# GuitarMultiEffect.net
KiCad netlist of a schematic drawn in EasyEDA
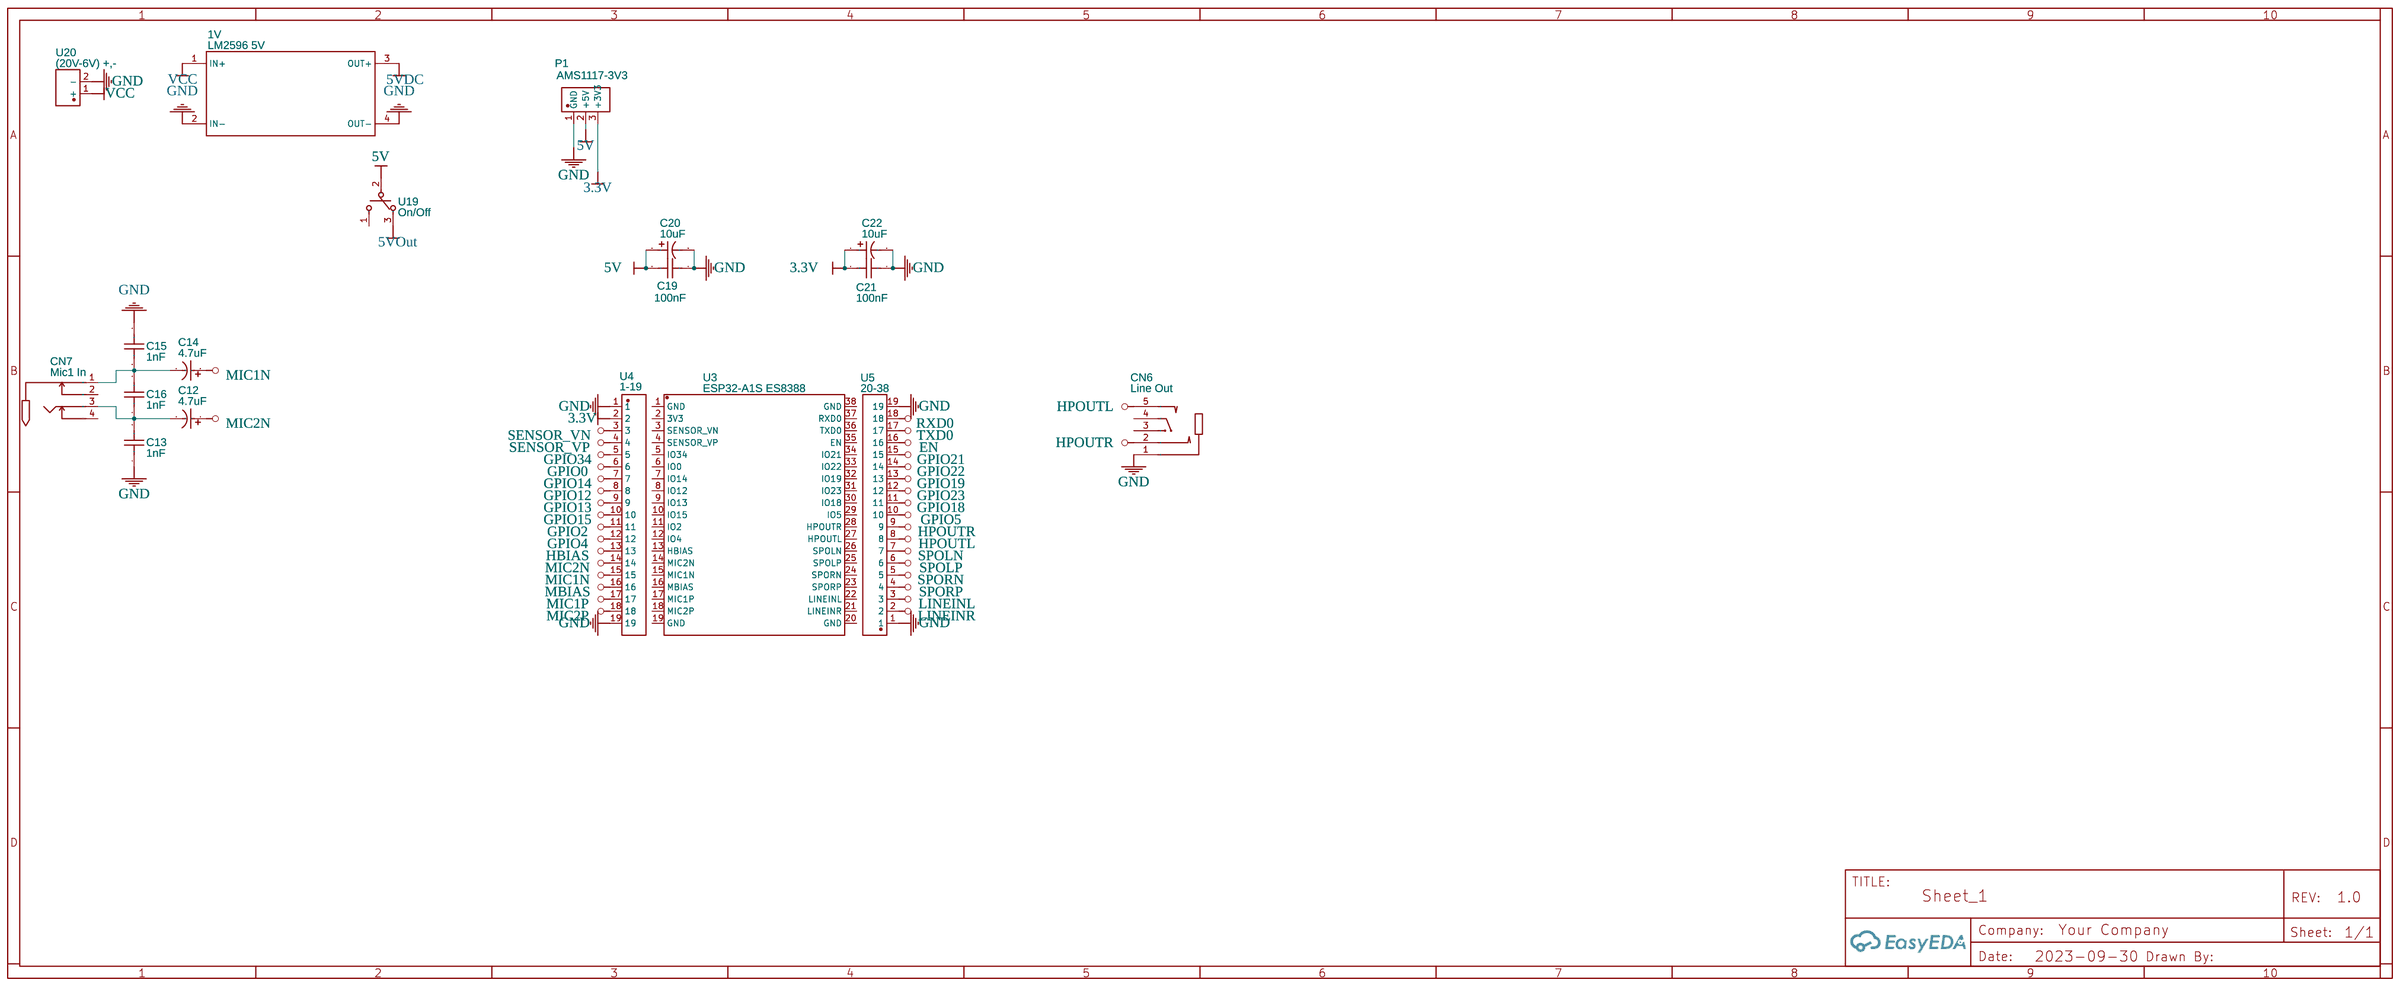
[diagram p0: schematic sheet]

(export (version "E")
  (design (tool "Eeschema 10.0.6"))
  (components
    (comp (ref "1V") (value "LM2596 5V") (libsource (lib "") (part "LM2596")))
    (comp (ref "C12")
      (value "4.7uF")
      (fields
        (field (name "Manufacturer Part") "KM475M050D11RR0VH2FP0")
        (field (name "Manufacturer") "CX(承兴)")
      )
      (libsource (lib "") (part "4.7uF 50V 5*11"))
    )
    (comp (ref "C13")
      (value "1nF")
      (fields (field (name "Manufacturer Part") "R08B1B102KN0B0S0N0") (field (name "Manufacturer") "STE(松田)"))
      (libsource (lib "") (part "R08B1B102KN0B0S0N0_1"))
    )
    (comp (ref "C14")
      (value "4.7uF")
      (fields
        (field (name "Manufacturer Part") "KM475M050D11RR0VH2FP0")
        (field (name "Manufacturer") "CX(承兴)")
      )
      (libsource (lib "") (part "4.7uF 50V 5*11"))
    )
    (comp (ref "C15")
      (value "1nF")
      (fields (field (name "Manufacturer Part") "R08B1B102KN0B0S0N0") (field (name "Manufacturer") "STE(松田)"))
      (libsource (lib "") (part "R08B1B102KN0B0S0N0"))
    )
    (comp (ref "C16")
      (value "1nF")
      (fields (field (name "Manufacturer Part") "R08B1B102KN0B0S0N0") (field (name "Manufacturer") "STE(松田)"))
      (libsource (lib "") (part "R08B1B102KN0B0S0N0_1"))
    )
    (comp (ref "C19")
      (value "100nF")
      (fields (field (name "Manufacturer Part") "CL112J103J0501") (field (name "Manufacturer") "KYET(科雅)"))
      (libsource (lib "") (part "CL112J103J0501"))
    )
    (comp (ref "C20")
      (value "10uF")
      (fields (field (name "Manufacturer Part") "50V10uF CD110") (field (name "Manufacturer") "HRK(鸿瑞凯电子)"))
      (libsource (lib "") (part "50V10UF CD110_C2960373"))
    )
    (comp (ref "C21")
      (value "100nF")
      (fields (field (name "Manufacturer Part") "CL112J103J0501") (field (name "Manufacturer") "KYET(科雅)"))
      (libsource (lib "") (part "CL112J103J0501"))
    )
    (comp (ref "C22")
      (value "10uF")
      (fields (field (name "Manufacturer Part") "50V10uF CD110") (field (name "Manufacturer") "HRK(鸿瑞凯电子)"))
      (libsource (lib "") (part "50V10UF CD110_C2960373"))
    )
    (comp (ref "CN6")
      (value "Line Out")
      (fields
        (field (name "Manufacturer Part") "PJ-3062-HD-R")
        (field (name "Manufacturer") "XKB Connectivity(中国星坤)")
      )
      (libsource (lib "") (part "PJ-3062-HD-R"))
    )
    (comp (ref "CN7")
      (value "Mic1 In")
      (fields (field (name "Manufacturer Part") "CK6.35-3+15-6") (field (name "Manufacturer") "JINJIA(金佳)"))
      (libsource (lib "") (part "CK6.35-3+15-6"))
    )
    (comp (ref "P1")
      (value "AMS1117-3V3")
      (fields (field (name "Manufacturer Part") "M3025V-1x6P") (field (name "Manufacturer") "XFCN"))
      (libsource (lib "") (part "Header 1x3"))
    )
    (comp (ref "U3")
      (value "ESP32-A1S ES8388")
      (fields (field (name "Manufacturer Part") "ESP32-A1S") (field (name "Manufacturer") "Ai-Thinker"))
      (libsource (lib "") (part "ESP32-A1S"))
    )
    (comp (ref "U4")
      (value "1-19")
      (fields
        (field (name "Manufacturer Part") "X1311WV-19J-C18D27")
        (field (name "Manufacturer") "XKB Connectivity(中国星坤)")
      )
      (libsource (lib "") (part "X1311WV-19J-C18D27"))
    )
    (comp (ref "U5")
      (value "20-38")
      (fields
        (field (name "Manufacturer Part") "X1311WV-19J-C18D27")
        (field (name "Manufacturer") "XKB Connectivity(中国星坤)")
      )
      (libsource (lib "") (part "X1311WV-19J-C18D27_1"))
    )
    (comp (ref "U19")
      (value "On/Off")
      (fields
        (field (name "Manufacturer Part") "MT-0-103-A101-M200-RS+PJ")
        (field (name "Manufacturer") "YUEN FUNG(源丰)")
      )
      (libsource (lib "") (part "MT-0-103-A101-M200-RS+PJ"))
    )
    (comp (ref "U20")
      (value "(20V-6V) +,-")
      (fields
        (field (name "Manufacturer Part") "DB128L-5.08-2P-GN-S")
        (field (name "Manufacturer") "DIBO(地博电气)")
      )
      (libsource (lib "") (part "DB128L-5.08-2P"))
    )
  )
  (nets
    (net (code "1") (name "3.3V") (class "Default")
      (node (ref "C21") (pin "2") (pinfunction "2_2") (pintype "unspecified"))
      (node (ref "C22") (pin "1") (pinfunction "1_1") (pintype "input"))
      (node (ref "P1") (pin "3") (pinfunction "+3V3_3") (pintype "unspecified"))
      (node (ref "U4") (pin "2") (pinfunction "2_2") (pintype "unspecified"))
    )
    (net (code "2") (name "5V") (class "Default")
      (node (ref "C19") (pin "2") (pinfunction "2_2") (pintype "unspecified"))
      (node (ref "C20") (pin "1") (pinfunction "1_1") (pintype "input"))
      (node (ref "P1") (pin "2") (pinfunction "+5V_2") (pintype "unspecified"))
      (node (ref "U19") (pin "2") (pinfunction "2_2") (pintype "unspecified"))
    )
    (net (code "3") (name "5VDC") (class "Default")
      (node (ref "1V") (pin "3") (pinfunction "OUT+_3") (pintype "unspecified"))
    )
    (net (code "4") (name "5VOut") (class "Default")
      (node (ref "U19") (pin "3") (pinfunction "3_3") (pintype "unspecified"))
    )
    (net (code "5") (name "EN") (class "Default")
      (node (ref "U5") (pin "16") (pinfunction "16_16") (pintype "unspecified"))
    )
    (net (code "6") (name "GND") (class "Default")
      (node (ref "1V") (pin "2") (pinfunction "IN-_2") (pintype "unspecified"))
      (node (ref "1V") (pin "4") (pinfunction "OUT-_4") (pintype "unspecified"))
      (node (ref "C13") (pin "1") (pinfunction "1_1") (pintype "unspecified"))
      (node (ref "C15") (pin "1") (pinfunction "1_1") (pintype "unspecified"))
      (node (ref "C19") (pin "1") (pinfunction "1_1") (pintype "unspecified"))
      (node (ref "C20") (pin "2") (pinfunction "2_2") (pintype "input"))
      (node (ref "C21") (pin "1") (pinfunction "1_1") (pintype "unspecified"))
      (node (ref "C22") (pin "2") (pinfunction "2_2") (pintype "input"))
      (node (ref "CN6") (pin "1") (pinfunction "1_1") (pintype "unspecified"))
      (node (ref "P1") (pin "1") (pinfunction "GND_1") (pintype "unspecified"))
      (node (ref "U20") (pin "2") (pinfunction "-_2") (pintype "unspecified"))
      (node (ref "U4") (pin "1") (pinfunction "1_1") (pintype "unspecified"))
      (node (ref "U4") (pin "19") (pinfunction "19_19") (pintype "unspecified"))
      (node (ref "U5") (pin "1") (pinfunction "1_1") (pintype "unspecified"))
      (node (ref "U5") (pin "19") (pinfunction "19_19") (pintype "unspecified"))
    )
    (net (code "7") (name "GPIO0") (class "Default")
      (node (ref "U4") (pin "6") (pinfunction "6_6") (pintype "unspecified"))
    )
    (net (code "8") (name "GPIO2") (class "Default")
      (node (ref "U4") (pin "11") (pinfunction "11_11") (pintype "unspecified"))
    )
    (net (code "9") (name "GPIO4") (class "Default")
      (node (ref "U4") (pin "12") (pinfunction "12_12") (pintype "unspecified"))
    )
    (net (code "10") (name "GPIO5") (class "Default")
      (node (ref "U5") (pin "10") (pinfunction "10_10") (pintype "unspecified"))
    )
    (net (code "11") (name "GPIO12") (class "Default")
      (node (ref "U4") (pin "8") (pinfunction "8_8") (pintype "unspecified"))
    )
    (net (code "12") (name "GPIO13") (class "Default")
      (node (ref "U4") (pin "9") (pinfunction "9_9") (pintype "unspecified"))
    )
    (net (code "13") (name "GPIO14") (class "Default")
      (node (ref "U4") (pin "7") (pinfunction "7_7") (pintype "unspecified"))
    )
    (net (code "14") (name "GPIO15") (class "Default")
      (node (ref "U4") (pin "10") (pinfunction "10_10") (pintype "unspecified"))
    )
    (net (code "15") (name "GPIO18") (class "Default")
      (node (ref "U5") (pin "11") (pinfunction "11_11") (pintype "unspecified"))
    )
    (net (code "16") (name "GPIO19") (class "Default")
      (node (ref "U5") (pin "13") (pinfunction "13_13") (pintype "unspecified"))
    )
    (net (code "17") (name "GPIO21") (class "Default")
      (node (ref "U5") (pin "15") (pinfunction "15_15") (pintype "unspecified"))
    )
    (net (code "18") (name "GPIO22") (class "Default")
      (node (ref "U5") (pin "14") (pinfunction "14_14") (pintype "unspecified"))
    )
    (net (code "19") (name "GPIO23") (class "Default")
      (node (ref "U5") (pin "12") (pinfunction "12_12") (pintype "unspecified"))
    )
    (net (code "20") (name "GPIO34") (class "Default")
      (node (ref "U4") (pin "5") (pinfunction "5_5") (pintype "unspecified"))
    )
    (net (code "21") (name "HBIAS") (class "Default")
      (node (ref "U4") (pin "13") (pinfunction "13_13") (pintype "unspecified"))
    )
    (net (code "22") (name "HPOUTL") (class "Default")
      (node (ref "CN6") (pin "5") (pinfunction "5_5") (pintype "unspecified"))
      (node (ref "U5") (pin "8") (pinfunction "8_8") (pintype "unspecified"))
    )
    (net (code "23") (name "HPOUTR") (class "Default")
      (node (ref "CN6") (pin "2") (pinfunction "2_2") (pintype "unspecified"))
      (node (ref "U5") (pin "9") (pinfunction "9_9") (pintype "unspecified"))
    )
    (net (code "24") (name "LINEINL") (class "Default")
      (node (ref "U5") (pin "3") (pinfunction "3_3") (pintype "unspecified"))
    )
    (net (code "25") (name "LINEINR") (class "Default")
      (node (ref "U5") (pin "2") (pinfunction "2_2") (pintype "unspecified"))
    )
    (net (code "26") (name "MBIAS") (class "Default")
      (node (ref "U4") (pin "16") (pinfunction "16_16") (pintype "unspecified"))
    )
    (net (code "27") (name "MIC1N") (class "Default")
      (node (ref "C14") (pin "1") (pinfunction "1_1") (pintype "input"))
      (node (ref "U4") (pin "15") (pinfunction "15_15") (pintype "unspecified"))
    )
    (net (code "28") (name "MIC1P") (class "Default")
      (node (ref "U4") (pin "17") (pinfunction "17_17") (pintype "unspecified"))
    )
    (net (code "29") (name "MIC2N") (class "Default")
      (node (ref "C12") (pin "1") (pinfunction "1_1") (pintype "input"))
      (node (ref "U4") (pin "14") (pinfunction "14_14") (pintype "unspecified"))
    )
    (net (code "30") (name "MIC2P") (class "Default")
      (node (ref "U4") (pin "18") (pinfunction "18_18") (pintype "unspecified"))
    )
    (net (code "31") (name "Net-(C12-Pad2)") (class "Default")
      (node (ref "C12") (pin "2") (pinfunction "2_2") (pintype "input"))
      (node (ref "C13") (pin "2") (pinfunction "2_2") (pintype "unspecified"))
      (node (ref "C16") (pin "1") (pinfunction "1_1") (pintype "unspecified"))
      (node (ref "CN7") (pin "3") (pinfunction "3_3") (pintype "input"))
    )
    (net (code "32") (name "Net-(C14-Pad2)") (class "Default")
      (node (ref "C14") (pin "2") (pinfunction "2_2") (pintype "input"))
      (node (ref "C15") (pin "2") (pinfunction "2_2") (pintype "unspecified"))
      (node (ref "C16") (pin "2") (pinfunction "2_2") (pintype "unspecified"))
      (node (ref "CN7") (pin "1") (pinfunction "1_1") (pintype "input"))
    )
    (net (code "33") (name "RXD0") (class "Default")
      (node (ref "U5") (pin "18") (pinfunction "18_18") (pintype "unspecified"))
    )
    (net (code "34") (name "SENSOR_VN") (class "Default")
      (node (ref "U4") (pin "3") (pinfunction "3_3") (pintype "unspecified"))
    )
    (net (code "35") (name "SENSOR_VP") (class "Default")
      (node (ref "U4") (pin "4") (pinfunction "4_4") (pintype "unspecified"))
    )
    (net (code "36") (name "SPOLN") (class "Default")
      (node (ref "U5") (pin "7") (pinfunction "7_7") (pintype "unspecified"))
    )
    (net (code "37") (name "SPOLP") (class "Default")
      (node (ref "U5") (pin "6") (pinfunction "6_6") (pintype "unspecified"))
    )
    (net (code "38") (name "SPORN") (class "Default")
      (node (ref "U5") (pin "5") (pinfunction "5_5") (pintype "unspecified"))
    )
    (net (code "39") (name "SPORP") (class "Default")
      (node (ref "U5") (pin "4") (pinfunction "4_4") (pintype "unspecified"))
    )
    (net (code "40") (name "TXD0") (class "Default")
      (node (ref "U5") (pin "17") (pinfunction "17_17") (pintype "unspecified"))
    )
    (net (code "41") (name "VCC") (class "Default")
      (node (ref "1V") (pin "1") (pinfunction "IN+_1") (pintype "unspecified"))
      (node (ref "U20") (pin "1") (pinfunction "+_1") (pintype "unspecified"))
    )
    (net (code "42") (name "unconnected-(CN6-Pad3)") (class "Default")
      (node (ref "CN6") (pin "3") (pinfunction "3_3") (pintype "unspecified"))
    )
    (net (code "43") (name "unconnected-(CN6-Pad4)") (class "Default")
      (node (ref "CN6") (pin "4") (pinfunction "4_4") (pintype "unspecified"))
    )
    (net (code "44") (name "unconnected-(CN7-Pad2)") (class "Default")
      (node (ref "CN7") (pin "2") (pinfunction "2_2") (pintype "input"))
    )
    (net (code "45") (name "unconnected-(CN7-Pad4)") (class "Default")
      (node (ref "CN7") (pin "4") (pinfunction "4_4") (pintype "input"))
    )
    (net (code "46") (name "unconnected-(U3-3V3-Pad2)") (class "Default")
      (node (ref "U3") (pin "2") (pinfunction "3V3_2") (pintype "unspecified"))
    )
    (net (code "47") (name "unconnected-(U3-EN-Pad35)") (class "Default")
      (node (ref "U3") (pin "35") (pinfunction "EN_35") (pintype "unspecified"))
    )
    (net (code "48") (name "unconnected-(U3-GND-Pad1)") (class "Default")
      (node (ref "U3") (pin "1") (pinfunction "GND_1") (pintype "unspecified"))
    )
    (net (code "49") (name "unconnected-(U3-GND-Pad19)") (class "Default")
      (node (ref "U3") (pin "19") (pinfunction "GND_19") (pintype "unspecified"))
    )
    (net (code "50") (name "unconnected-(U3-GND-Pad20)") (class "Default")
      (node (ref "U3") (pin "20") (pinfunction "GND_20") (pintype "unspecified"))
    )
    (net (code "51") (name "unconnected-(U3-GND-Pad38)") (class "Default")
      (node (ref "U3") (pin "38") (pinfunction "GND_38") (pintype "unspecified"))
    )
    (net (code "52") (name "unconnected-(U3-HBIAS-Pad13)") (class "Default")
      (node (ref "U3") (pin "13") (pinfunction "HBIAS_13") (pintype "unspecified"))
    )
    (net (code "53") (name "unconnected-(U3-HPOUTL-Pad27)") (class "Default")
      (node (ref "U3") (pin "27") (pinfunction "HPOUTL_27") (pintype "unspecified"))
    )
    (net (code "54") (name "unconnected-(U3-HPOUTR-Pad28)") (class "Default")
      (node (ref "U3") (pin "28") (pinfunction "HPOUTR_28") (pintype "unspecified"))
    )
    (net (code "55") (name "unconnected-(U3-IO0-Pad6)") (class "Default")
      (node (ref "U3") (pin "6") (pinfunction "IO0_6") (pintype "unspecified"))
    )
    (net (code "56") (name "unconnected-(U3-IO2-Pad11)") (class "Default")
      (node (ref "U3") (pin "11") (pinfunction "IO2_11") (pintype "unspecified"))
    )
    (net (code "57") (name "unconnected-(U3-IO4-Pad12)") (class "Default")
      (node (ref "U3") (pin "12") (pinfunction "IO4_12") (pintype "unspecified"))
    )
    (net (code "58") (name "unconnected-(U3-IO5-Pad29)") (class "Default")
      (node (ref "U3") (pin "29") (pinfunction "IO5_29") (pintype "unspecified"))
    )
    (net (code "59") (name "unconnected-(U3-IO12-Pad8)") (class "Default")
      (node (ref "U3") (pin "8") (pinfunction "IO12_8") (pintype "unspecified"))
    )
    (net (code "60") (name "unconnected-(U3-IO13-Pad9)") (class "Default")
      (node (ref "U3") (pin "9") (pinfunction "IO13_9") (pintype "unspecified"))
    )
    (net (code "61") (name "unconnected-(U3-IO14-Pad7)") (class "Default")
      (node (ref "U3") (pin "7") (pinfunction "IO14_7") (pintype "unspecified"))
    )
    (net (code "62") (name "unconnected-(U3-IO15-Pad10)") (class "Default")
      (node (ref "U3") (pin "10") (pinfunction "IO15_10") (pintype "unspecified"))
    )
    (net (code "63") (name "unconnected-(U3-IO18-Pad30)") (class "Default")
      (node (ref "U3") (pin "30") (pinfunction "IO18_30") (pintype "unspecified"))
    )
    (net (code "64") (name "unconnected-(U3-IO19-Pad32)") (class "Default")
      (node (ref "U3") (pin "32") (pinfunction "IO19_32") (pintype "unspecified"))
    )
    (net (code "65") (name "unconnected-(U3-IO21-Pad34)") (class "Default")
      (node (ref "U3") (pin "34") (pinfunction "IO21_34") (pintype "unspecified"))
    )
    (net (code "66") (name "unconnected-(U3-IO22-Pad33)") (class "Default")
      (node (ref "U3") (pin "33") (pinfunction "IO22_33") (pintype "unspecified"))
    )
    (net (code "67") (name "unconnected-(U3-IO23-Pad31)") (class "Default")
      (node (ref "U3") (pin "31") (pinfunction "IO23_31") (pintype "unspecified"))
    )
    (net (code "68") (name "unconnected-(U3-IO34-Pad5)") (class "Default")
      (node (ref "U3") (pin "5") (pinfunction "IO34_5") (pintype "unspecified"))
    )
    (net (code "69") (name "unconnected-(U3-LINEINL-Pad22)") (class "Default")
      (node (ref "U3") (pin "22") (pinfunction "LINEINL_22") (pintype "unspecified"))
    )
    (net (code "70") (name "unconnected-(U3-LINEINR-Pad21)") (class "Default")
      (node (ref "U3") (pin "21") (pinfunction "LINEINR_21") (pintype "unspecified"))
    )
    (net (code "71") (name "unconnected-(U3-MBIAS-Pad16)") (class "Default")
      (node (ref "U3") (pin "16") (pinfunction "MBIAS_16") (pintype "unspecified"))
    )
    (net (code "72") (name "unconnected-(U3-MIC1N-Pad15)") (class "Default")
      (node (ref "U3") (pin "15") (pinfunction "MIC1N_15") (pintype "unspecified"))
    )
    (net (code "73") (name "unconnected-(U3-MIC1P-Pad17)") (class "Default")
      (node (ref "U3") (pin "17") (pinfunction "MIC1P_17") (pintype "unspecified"))
    )
    (net (code "74") (name "unconnected-(U3-MIC2N-Pad14)") (class "Default")
      (node (ref "U3") (pin "14") (pinfunction "MIC2N_14") (pintype "unspecified"))
    )
    (net (code "75") (name "unconnected-(U3-MIC2P-Pad18)") (class "Default")
      (node (ref "U3") (pin "18") (pinfunction "MIC2P_18") (pintype "unspecified"))
    )
    (net (code "76") (name "unconnected-(U3-RXD0-Pad37)") (class "Default")
      (node (ref "U3") (pin "37") (pinfunction "RXD0_37") (pintype "unspecified"))
    )
    (net (code "77") (name "unconnected-(U3-SENSOR_VN-Pad3)") (class "Default")
      (node (ref "U3") (pin "3") (pinfunction "SENSOR_VN_3") (pintype "unspecified"))
    )
    (net (code "78") (name "unconnected-(U3-SENSOR_VP-Pad4)") (class "Default")
      (node (ref "U3") (pin "4") (pinfunction "SENSOR_VP_4") (pintype "unspecified"))
    )
    (net (code "79") (name "unconnected-(U3-SPOLN-Pad26)") (class "Default")
      (node (ref "U3") (pin "26") (pinfunction "SPOLN_26") (pintype "unspecified"))
    )
    (net (code "80") (name "unconnected-(U3-SPOLP-Pad25)") (class "Default")
      (node (ref "U3") (pin "25") (pinfunction "SPOLP_25") (pintype "unspecified"))
    )
    (net (code "81") (name "unconnected-(U3-SPORN-Pad24)") (class "Default")
      (node (ref "U3") (pin "24") (pinfunction "SPORN_24") (pintype "unspecified"))
    )
    (net (code "82") (name "unconnected-(U3-SPORP-Pad23)") (class "Default")
      (node (ref "U3") (pin "23") (pinfunction "SPORP_23") (pintype "unspecified"))
    )
    (net (code "83") (name "unconnected-(U3-TXD0-Pad36)") (class "Default")
      (node (ref "U3") (pin "36") (pinfunction "TXD0_36") (pintype "unspecified"))
    )
    (net (code "84") (name "unconnected-(U19-Pad1)") (class "Default")
      (node (ref "U19") (pin "1") (pinfunction "1_1") (pintype "unspecified"))
    )
  )
)
